# SH2_-_CONNECTORS.net
KiCad netlist of a schematic drawn in Altium Designer
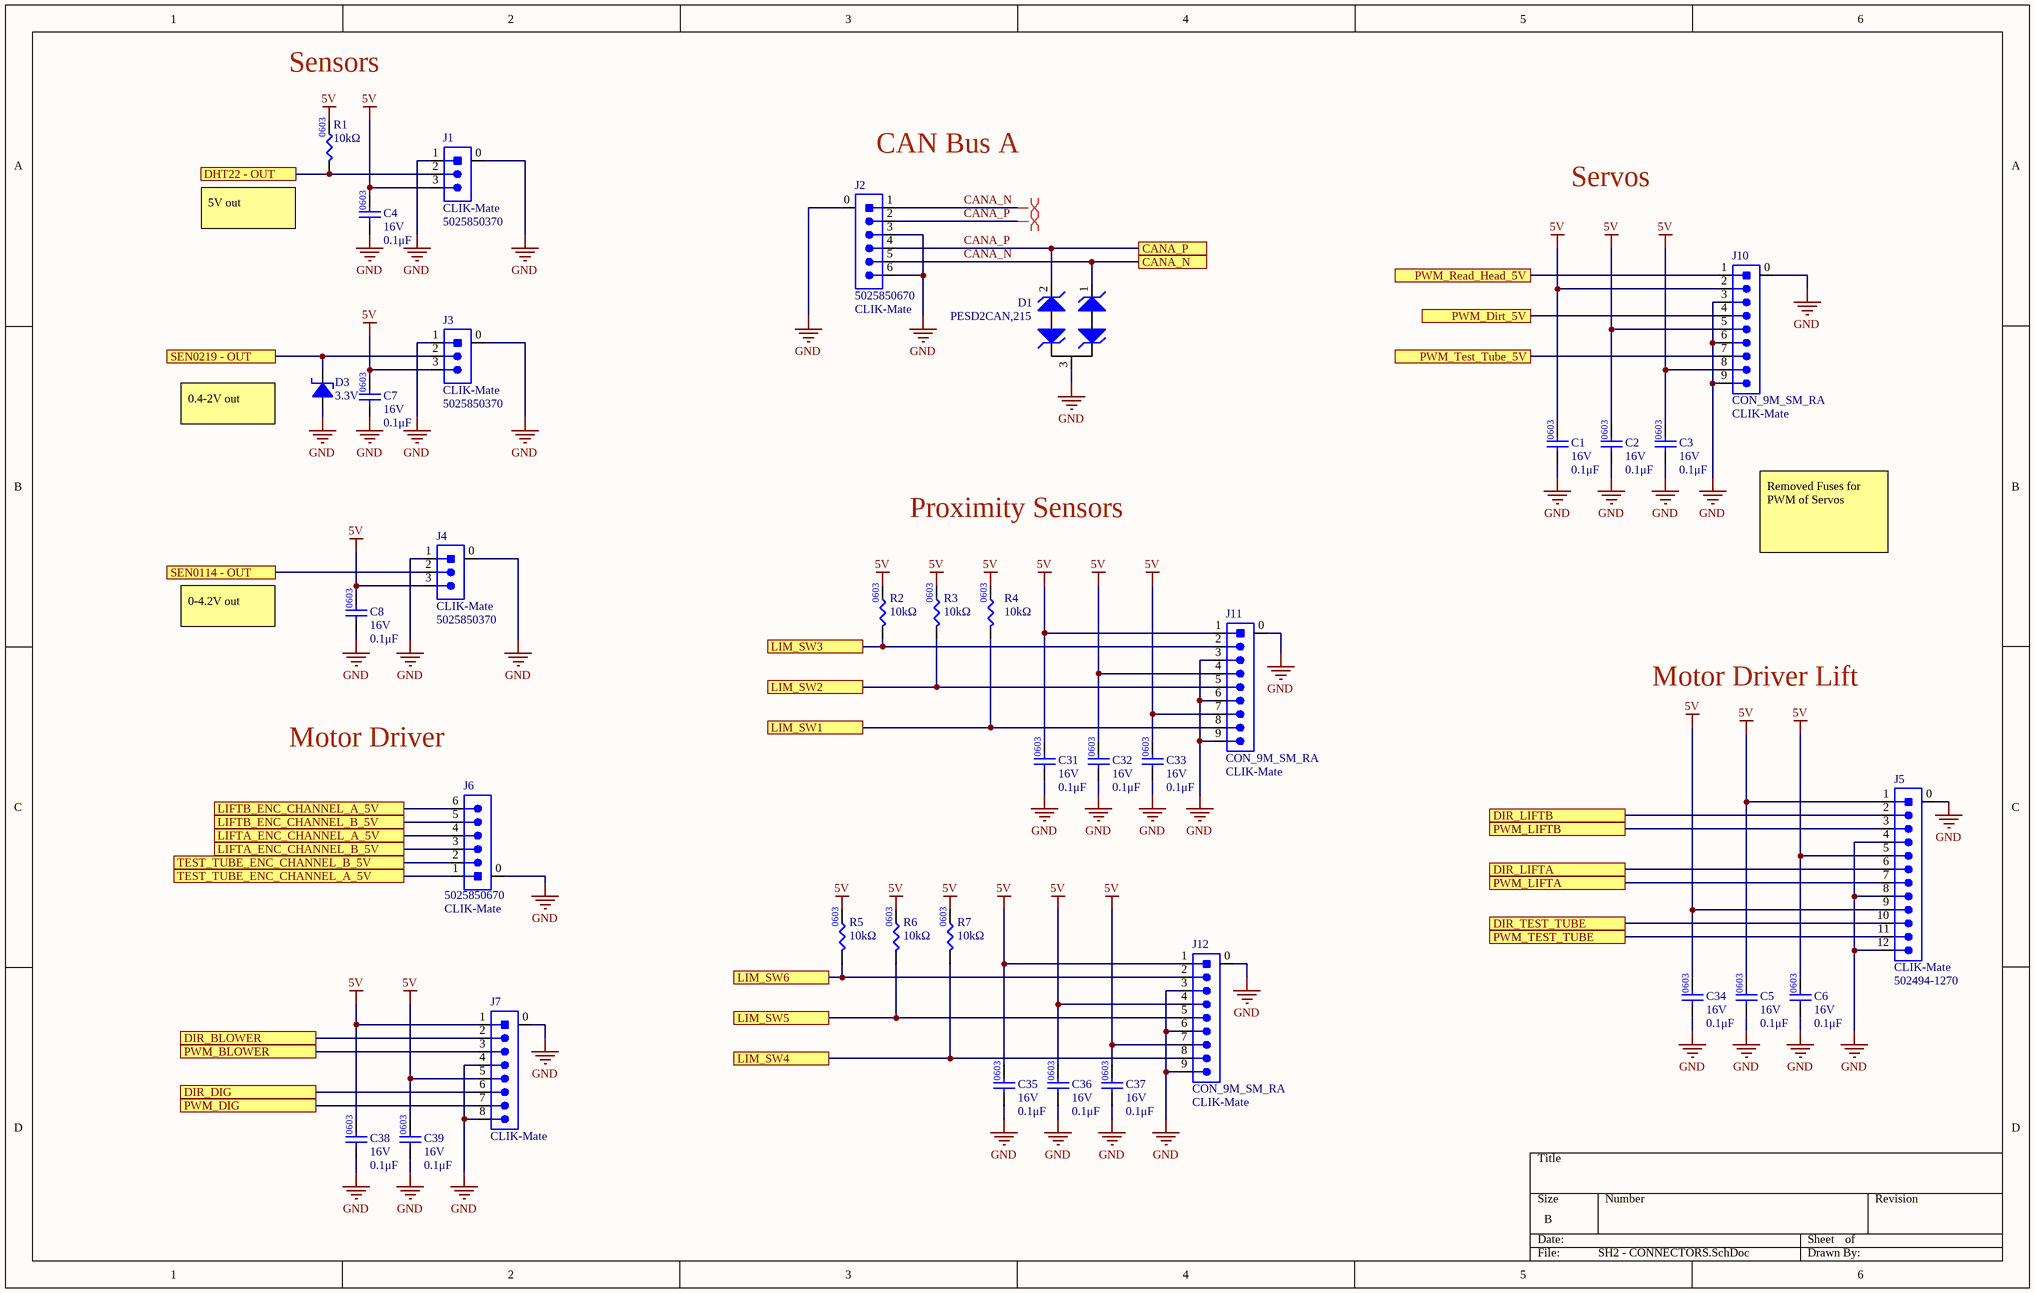
[diagram p0: SH2 - CONNECTORS.SchDoc]

(export (version "E")
  (design (tool "Eeschema 10.0.6"))
  (components
    (comp (ref "C1")
      (value "0.1μF")
      (footprint "CAP0603")
      (description "CAP CER 0.1UF 16V X7R 0603")
      (fields (field (name "VOLTAGE RATING") "16V") (field (name "Comment") "CAP_0.1uF_16V_0603"))
      (libsource (lib "UWRT_Schematic_Library_2020") (part "CAP_0.1uF_16V_0603"))
    )
    (comp (ref "C2")
      (value "0.1μF")
      (footprint "CAP0603")
      (description "CAP CER 0.1UF 16V X7R 0603")
      (fields (field (name "VOLTAGE RATING") "16V") (field (name "Comment") "CAP_0.1uF_16V_0603"))
      (libsource (lib "UWRT_Schematic_Library_2020") (part "CAP_0.1uF_16V_0603"))
    )
    (comp (ref "C3")
      (value "0.1μF")
      (footprint "CAP0603")
      (description "CAP CER 0.1UF 16V X7R 0603")
      (fields (field (name "VOLTAGE RATING") "16V") (field (name "Comment") "CAP_0.1uF_16V_0603"))
      (libsource (lib "UWRT_Schematic_Library_2020") (part "CAP_0.1uF_16V_0603"))
    )
    (comp (ref "C4")
      (value "0.1μF")
      (footprint "CAP0603")
      (description "CAP CER 0.1UF 16V X7R 0603")
      (fields (field (name "VOLTAGE RATING") "16V") (field (name "Comment") "CAP_0.1uF_16V_0603"))
      (libsource (lib "UWRT_Schematic_Library_2020") (part "CAP_0.1uF_16V_0603"))
    )
    (comp (ref "C5")
      (value "0.1μF")
      (footprint "CAP0603")
      (description "CAP CER 0.1UF 16V X7R 0603")
      (fields (field (name "VOLTAGE RATING") "16V") (field (name "Comment") "CAP_0.1uF_16V_0603"))
      (libsource (lib "UWRT_Schematic_Library_2020") (part "CAP_0.1uF_16V_0603"))
    )
    (comp (ref "C6")
      (value "0.1μF")
      (footprint "CAP0603")
      (description "CAP CER 0.1UF 16V X7R 0603")
      (fields (field (name "VOLTAGE RATING") "16V") (field (name "Comment") "CAP_0.1uF_16V_0603"))
      (libsource (lib "UWRT_Schematic_Library_2020") (part "CAP_0.1uF_16V_0603"))
    )
    (comp (ref "C7")
      (value "0.1μF")
      (footprint "CAP0603")
      (description "CAP CER 0.1UF 16V X7R 0603")
      (fields (field (name "VOLTAGE RATING") "16V") (field (name "Comment") "CAP_0.1uF_16V_0603"))
      (libsource (lib "UWRT_Schematic_Library_2020") (part "CAP_0.1uF_16V_0603"))
    )
    (comp (ref "C8")
      (value "0.1μF")
      (footprint "CAP0603")
      (description "CAP CER 0.1UF 16V X7R 0603")
      (fields (field (name "VOLTAGE RATING") "16V") (field (name "Comment") "CAP_0.1uF_16V_0603"))
      (libsource (lib "UWRT_Schematic_Library_2020") (part "CAP_0.1uF_16V_0603"))
    )
    (comp (ref "C31")
      (value "0.1μF")
      (footprint "CAP0603")
      (description "CAP CER 0.1UF 16V X7R 0603")
      (fields (field (name "VOLTAGE RATING") "16V") (field (name "Comment") "CAP_0.1uF_16V_0603"))
      (libsource (lib "UWRT_Schematic_Library_2020") (part "CAP_0.1uF_16V_0603"))
    )
    (comp (ref "C32")
      (value "0.1μF")
      (footprint "CAP0603")
      (description "CAP CER 0.1UF 16V X7R 0603")
      (fields (field (name "VOLTAGE RATING") "16V") (field (name "Comment") "CAP_0.1uF_16V_0603"))
      (libsource (lib "UWRT_Schematic_Library_2020") (part "CAP_0.1uF_16V_0603"))
    )
    (comp (ref "C33")
      (value "0.1μF")
      (footprint "CAP0603")
      (description "CAP CER 0.1UF 16V X7R 0603")
      (fields (field (name "VOLTAGE RATING") "16V") (field (name "Comment") "CAP_0.1uF_16V_0603"))
      (libsource (lib "UWRT_Schematic_Library_2020") (part "CAP_0.1uF_16V_0603"))
    )
    (comp (ref "C34")
      (value "0.1μF")
      (footprint "CAP0603")
      (description "CAP CER 0.1UF 16V X7R 0603")
      (fields (field (name "VOLTAGE RATING") "16V") (field (name "Comment") "CAP_0.1uF_16V_0603"))
      (libsource (lib "UWRT_Schematic_Library_2020") (part "CAP_0.1uF_16V_0603"))
    )
    (comp (ref "C35")
      (value "0.1μF")
      (footprint "CAP0603")
      (description "CAP CER 0.1UF 16V X7R 0603")
      (fields (field (name "VOLTAGE RATING") "16V") (field (name "Comment") "CAP_0.1uF_16V_0603"))
      (libsource (lib "UWRT_Schematic_Library_2020") (part "CAP_0.1uF_16V_0603"))
    )
    (comp (ref "C36")
      (value "0.1μF")
      (footprint "CAP0603")
      (description "CAP CER 0.1UF 16V X7R 0603")
      (fields (field (name "VOLTAGE RATING") "16V") (field (name "Comment") "CAP_0.1uF_16V_0603"))
      (libsource (lib "UWRT_Schematic_Library_2020") (part "CAP_0.1uF_16V_0603"))
    )
    (comp (ref "C37")
      (value "0.1μF")
      (footprint "CAP0603")
      (description "CAP CER 0.1UF 16V X7R 0603")
      (fields (field (name "VOLTAGE RATING") "16V") (field (name "Comment") "CAP_0.1uF_16V_0603"))
      (libsource (lib "UWRT_Schematic_Library_2020") (part "CAP_0.1uF_16V_0603"))
    )
    (comp (ref "C38")
      (value "0.1μF")
      (footprint "CAP0603")
      (description "CAP CER 0.1UF 16V X7R 0603")
      (fields (field (name "VOLTAGE RATING") "16V") (field (name "Comment") "CAP_0.1uF_16V_0603"))
      (libsource (lib "UWRT_Schematic_Library_2020") (part "CAP_0.1uF_16V_0603"))
    )
    (comp (ref "C39")
      (value "0.1μF")
      (footprint "CAP0603")
      (description "CAP CER 0.1UF 16V X7R 0603")
      (fields (field (name "VOLTAGE RATING") "16V") (field (name "Comment") "CAP_0.1uF_16V_0603"))
      (libsource (lib "UWRT_Schematic_Library_2020") (part "CAP_0.1uF_16V_0603"))
    )
    (comp (ref "D1")
      (value "TVS_DIODE_CAN")
      (footprint "TVS_DIODE_CAN")
      (description "TVS DIODE 24V 41V SOT323-3")
      (fields (field (name "MANUFACTURER PART NUMBER 1") "PESD2CAN,215"))
      (libsource (lib "UWRT_Schematic_Library_2020") (part "TVS_DIODE_CAN"))
    )
    (comp (ref "D3")
      (value "DIO_ZENER_3V3")
      (footprint "DIO_ZENER_3V3")
      (description "DIODE ZENER 3.3V 200mW SOD323F")
      (fields (field (name "WORKING VOLTAGE") "3.3V"))
      (libsource (lib "UWRT_Schematic_Library_2020") (part "DIO_ZENER_3V3"))
    )
    (comp (ref "J1")
      (value "CON_3M_SM_RA")
      (footprint "MOLEX-5025850370")
      (description "CONN RCPT 3POS 0.059 TIN SMD R/A")
      (fields (field (name "FAMILY") "CLIK-Mate") (field (name "MANUFACTURER PART NUMBER 1") "5025850370"))
      (libsource (lib "UWRT_Schematic_Library_2020") (part "CON_3M_SM_RA"))
    )
    (comp (ref "J2")
      (value "CON_6M_SM_RA_1.5mm")
      (footprint "MOLEX-5025850670")
      (description "CONN HEADER SMD RIGHT ANGLE 1.5 MM PITCH")
      (fields (field (name "MANUFACTURER PART NUMBER 1") "5025850670") (field (name "FAMILY") "CLIK-Mate"))
      (libsource (lib "") (part "CON_6M_SM_RA_1.5mm_1"))
    )
    (comp (ref "J3")
      (value "CON_3M_SM_RA")
      (footprint "MOLEX-5025850370")
      (description "CONN RCPT 3POS 0.059 TIN SMD R/A")
      (fields (field (name "FAMILY") "CLIK-Mate") (field (name "MANUFACTURER PART NUMBER 1") "5025850370"))
      (libsource (lib "UWRT_Schematic_Library_2020") (part "CON_3M_SM_RA"))
    )
    (comp (ref "J4")
      (value "CON_3M_SM_RA")
      (footprint "MOLEX-5025850370")
      (description "CONN RCPT 3POS 0.059 TIN SMD R/A")
      (fields (field (name "FAMILY") "CLIK-Mate") (field (name "MANUFACTURER PART NUMBER 1") "5025850370"))
      (libsource (lib "UWRT_Schematic_Library_2020") (part "CON_3M_SM_RA"))
    )
    (comp (ref "J5")
      (value "CON_12M_SM_RA_2mm")
      (footprint "MOLEX-5024941270")
      (description "2.00mm Pitch CLIK-Mate Wire-to-Board PCB Receptacle, Single Row, Right-Angle, 12 Circuits")
      (fields
        (field (name "MANUFACTURER") "Molex")
        (field (name "MANUFACTURER PART NUMBER") "502494-1270")
        (field (name "FAMILY") "CLIK-Mate")
        (field (name "SUPPLIER PART NUMBER 1") "502494-1270")
      )
      (libsource (lib "UWRT_Schematic_Library_2020") (part "CON_12M_SM_RA_2mm"))
    )
    (comp (ref "J6")
      (value "CON_6M_SM_RA_1.5mm")
      (footprint "MOLEX-5025850670")
      (description "CONN HEADER SMD RIGHT ANGLE 1.5 MM PITCH")
      (fields (field (name "MANUFACTURER PART NUMBER 1") "5025850670") (field (name "FAMILY") "CLIK-Mate"))
      (libsource (lib "UWRT_Schematic_Library_2020") (part "CON_6M_SM_RA_1.5mm"))
    )
    (comp (ref "J7")
      (value "CON_8M_SM_RA")
      (footprint "5024430870")
      (description "CONN HEADER SMD VERTICAL 2 MM PITCH")
      (fields (field (name "FAMILY") "CLIK-Mate"))
      (libsource (lib "UWRT_Schematic_Library_2020") (part "CON_8M_SM"))
    )
    (comp (ref "J10")
      (value "CON_9M_SM_RA")
      (footprint "Molex-5025850970")
      (description "CONN RCPT 9POS CLIK-MATE 0.059 TIN SMD R/A")
      (fields (field (name "FAMILY") "CLIK-Mate"))
      (libsource (lib "UWRT_Schematic_Library_2020") (part "CON_9M_SM_RA"))
    )
    (comp (ref "J11")
      (value "CON_9M_SM_RA")
      (footprint "Molex-5025850970")
      (description "CONN RCPT 9POS CLIK-MATE 0.059 TIN SMD R/A")
      (fields (field (name "FAMILY") "CLIK-Mate"))
      (libsource (lib "UWRT_Schematic_Library_2020") (part "CON_9M_SM_RA"))
    )
    (comp (ref "J12")
      (value "CON_9M_SM_RA")
      (footprint "Molex-5025850970")
      (description "CONN RCPT 9POS CLIK-MATE 0.059 TIN SMD R/A")
      (fields (field (name "FAMILY") "CLIK-Mate"))
      (libsource (lib "UWRT_Schematic_Library_2020") (part "CON_9M_SM_RA"))
    )
    (comp (ref "R1")
      (value "10kΩ")
      (footprint "RES0603")
      (description "RES 10K OHM 5% 1/10W 0603")
      (fields (field (name "Comment") "RES_10kΩ_0603_5%"))
      (libsource (lib "UWRT_Schematic_Library_2020") (part "RES_10kΩ_0603_5%"))
    )
    (comp (ref "R2")
      (value "10kΩ")
      (footprint "RES0603")
      (description "RES 10K OHM 5% 1/10W 0603")
      (fields (field (name "Comment") "RES_10kΩ_0603_5%"))
      (libsource (lib "UWRT_Schematic_Library_2020") (part "RES_10kΩ_0603_5%"))
    )
    (comp (ref "R3")
      (value "10kΩ")
      (footprint "RES0603")
      (description "RES 10K OHM 5% 1/10W 0603")
      (fields (field (name "Comment") "RES_10kΩ_0603_5%"))
      (libsource (lib "UWRT_Schematic_Library_2020") (part "RES_10kΩ_0603_5%"))
    )
    (comp (ref "R4")
      (value "10kΩ")
      (footprint "RES0603")
      (description "RES 10K OHM 5% 1/10W 0603")
      (fields (field (name "Comment") "RES_10kΩ_0603_5%"))
      (libsource (lib "UWRT_Schematic_Library_2020") (part "RES_10kΩ_0603_5%"))
    )
    (comp (ref "R5")
      (value "10kΩ")
      (footprint "RES0603")
      (description "RES 10K OHM 5% 1/10W 0603")
      (fields (field (name "Comment") "RES_10kΩ_0603_5%"))
      (libsource (lib "UWRT_Schematic_Library_2020") (part "RES_10kΩ_0603_5%"))
    )
    (comp (ref "R6")
      (value "10kΩ")
      (footprint "RES0603")
      (description "RES 10K OHM 5% 1/10W 0603")
      (fields (field (name "Comment") "RES_10kΩ_0603_5%"))
      (libsource (lib "UWRT_Schematic_Library_2020") (part "RES_10kΩ_0603_5%"))
    )
    (comp (ref "R7")
      (value "10kΩ")
      (footprint "RES0603")
      (description "RES 10K OHM 5% 1/10W 0603")
      (fields (field (name "Comment") "RES_10kΩ_0603_5%"))
      (libsource (lib "UWRT_Schematic_Library_2020") (part "RES_10kΩ_0603_5%"))
    )
  )
  (nets
    (net (code "1") (name "/CANA_N") (class "Default")
      (node (ref "D1") (pin "1") (pinfunction "1_1") (pintype "passive"))
      (node (ref "J2") (pin "1") (pinfunction "1_1") (pintype "passive"))
      (node (ref "J2") (pin "5") (pinfunction "5_5") (pintype "passive"))
    )
    (net (code "2") (name "/CANA_P") (class "Default")
      (node (ref "D1") (pin "2") (pinfunction "2_2") (pintype "passive"))
      (node (ref "J2") (pin "2") (pinfunction "2_2") (pintype "passive"))
      (node (ref "J2") (pin "4") (pinfunction "4_4") (pintype "passive"))
    )
    (net (code "3") (name "/DHT22 - OUT") (class "Default")
      (node (ref "J1") (pin "2") (pinfunction "2_2") (pintype "passive"))
      (node (ref "R1") (pin "1") (pinfunction "1_1") (pintype "passive"))
    )
    (net (code "4") (name "/DIR_BLOWER") (class "Default")
      (node (ref "J7") (pin "2") (pinfunction "2_2") (pintype "passive"))
    )
    (net (code "5") (name "/DIR_DIG") (class "Default")
      (node (ref "J7") (pin "6") (pinfunction "6_6") (pintype "passive"))
    )
    (net (code "6") (name "/DIR_LIFTA") (class "Default")
      (node (ref "J5") (pin "6") (pinfunction "6_6") (pintype "passive"))
    )
    (net (code "7") (name "/DIR_LIFTB") (class "Default")
      (node (ref "J5") (pin "2") (pinfunction "2_2") (pintype "passive"))
    )
    (net (code "8") (name "/DIR_TEST_TUBE") (class "Default")
      (node (ref "J5") (pin "10") (pinfunction "10_10") (pintype "passive"))
    )
    (net (code "9") (name "/LIFTA_ENC_CHANNEL_A_5V") (class "Default")
      (node (ref "J6") (pin "4") (pinfunction "4_4") (pintype "passive"))
    )
    (net (code "10") (name "/LIFTA_ENC_CHANNEL_B_5V") (class "Default")
      (node (ref "J6") (pin "3") (pinfunction "3_3") (pintype "passive"))
    )
    (net (code "11") (name "/LIFTB_ENC_CHANNEL_A_5V") (class "Default")
      (node (ref "J6") (pin "6") (pinfunction "6_6") (pintype "passive"))
    )
    (net (code "12") (name "/LIFTB_ENC_CHANNEL_B_5V") (class "Default")
      (node (ref "J6") (pin "5") (pinfunction "5_5") (pintype "passive"))
    )
    (net (code "13") (name "/LIM_SW1") (class "Default")
      (node (ref "J11") (pin "8") (pinfunction "6_8") (pintype "passive"))
      (node (ref "R4") (pin "1") (pinfunction "1_1") (pintype "passive"))
    )
    (net (code "14") (name "/LIM_SW2") (class "Default")
      (node (ref "J11") (pin "5") (pinfunction "5_5") (pintype "passive"))
      (node (ref "R3") (pin "1") (pinfunction "1_1") (pintype "passive"))
    )
    (net (code "15") (name "/LIM_SW3") (class "Default")
      (node (ref "J11") (pin "2") (pinfunction "2_2") (pintype "passive"))
      (node (ref "R2") (pin "1") (pinfunction "1_1") (pintype "passive"))
    )
    (net (code "16") (name "/LIM_SW4") (class "Default")
      (node (ref "J12") (pin "8") (pinfunction "6_8") (pintype "passive"))
      (node (ref "R7") (pin "1") (pinfunction "1_1") (pintype "passive"))
    )
    (net (code "17") (name "/LIM_SW5") (class "Default")
      (node (ref "J12") (pin "5") (pinfunction "5_5") (pintype "passive"))
      (node (ref "R6") (pin "1") (pinfunction "1_1") (pintype "passive"))
    )
    (net (code "18") (name "/LIM_SW6") (class "Default")
      (node (ref "J12") (pin "2") (pinfunction "2_2") (pintype "passive"))
      (node (ref "R5") (pin "1") (pinfunction "1_1") (pintype "passive"))
    )
    (net (code "19") (name "/PWM_BLOWER") (class "Default")
      (node (ref "J7") (pin "3") (pinfunction "3_3") (pintype "passive"))
    )
    (net (code "20") (name "/PWM_DIG") (class "Default")
      (node (ref "J7") (pin "7") (pinfunction "6_7") (pintype "passive"))
    )
    (net (code "21") (name "/PWM_Dirt_5V") (class "Default")
      (node (ref "J10") (pin "4") (pinfunction "4_4") (pintype "passive"))
    )
    (net (code "22") (name "/PWM_LIFTA") (class "Default")
      (node (ref "J5") (pin "7") (pinfunction "6_7") (pintype "passive"))
    )
    (net (code "23") (name "/PWM_LIFTB") (class "Default")
      (node (ref "J5") (pin "3") (pinfunction "3_3") (pintype "passive"))
    )
    (net (code "24") (name "/PWM_Read_Head_5V") (class "Default")
      (node (ref "J10") (pin "1") (pinfunction "1_1") (pintype "passive"))
    )
    (net (code "25") (name "/PWM_TEST_TUBE") (class "Default")
      (node (ref "J5") (pin "11") (pinfunction "11_11") (pintype "passive"))
    )
    (net (code "26") (name "/PWM_Test_Tube_5V") (class "Default")
      (node (ref "J10") (pin "7") (pinfunction "6_7") (pintype "passive"))
    )
    (net (code "27") (name "/SEN0114 - OUT") (class "Default")
      (node (ref "J4") (pin "2") (pinfunction "2_2") (pintype "passive"))
    )
    (net (code "28") (name "/SEN0219 - OUT") (class "Default")
      (node (ref "D3") (pin "2") (pinfunction "Cathode_2") (pintype "passive"))
      (node (ref "J3") (pin "2") (pinfunction "2_2") (pintype "passive"))
    )
    (net (code "29") (name "/TEST_TUBE_ENC_CHANNEL_A_5V") (class "Default")
      (node (ref "J6") (pin "1") (pinfunction "1_1") (pintype "passive"))
    )
    (net (code "30") (name "/TEST_TUBE_ENC_CHANNEL_B_5V") (class "Default")
      (node (ref "J6") (pin "2") (pinfunction "2_2") (pintype "passive"))
    )
    (net (code "31") (name "5V") (class "Default")
      (node (ref "C1") (pin "2") (pinfunction "2_2") (pintype "passive"))
      (node (ref "C2") (pin "2") (pinfunction "2_2") (pintype "passive"))
      (node (ref "C3") (pin "2") (pinfunction "2_2") (pintype "passive"))
      (node (ref "C31") (pin "2") (pinfunction "2_2") (pintype "passive"))
      (node (ref "C32") (pin "2") (pinfunction "2_2") (pintype "passive"))
      (node (ref "C33") (pin "2") (pinfunction "2_2") (pintype "passive"))
      (node (ref "C34") (pin "2") (pinfunction "2_2") (pintype "passive"))
      (node (ref "C35") (pin "2") (pinfunction "2_2") (pintype "passive"))
      (node (ref "C36") (pin "2") (pinfunction "2_2") (pintype "passive"))
      (node (ref "C37") (pin "2") (pinfunction "2_2") (pintype "passive"))
      (node (ref "C38") (pin "2") (pinfunction "2_2") (pintype "passive"))
      (node (ref "C39") (pin "2") (pinfunction "2_2") (pintype "passive"))
      (node (ref "C4") (pin "2") (pinfunction "2_2") (pintype "passive"))
      (node (ref "C5") (pin "2") (pinfunction "2_2") (pintype "passive"))
      (node (ref "C6") (pin "2") (pinfunction "2_2") (pintype "passive"))
      (node (ref "C7") (pin "2") (pinfunction "2_2") (pintype "passive"))
      (node (ref "C8") (pin "2") (pinfunction "2_2") (pintype "passive"))
      (node (ref "J1") (pin "3") (pinfunction "3_3") (pintype "passive"))
      (node (ref "J10") (pin "2") (pinfunction "2_2") (pintype "passive"))
      (node (ref "J10") (pin "5") (pinfunction "5_5") (pintype "passive"))
      (node (ref "J10") (pin "8") (pinfunction "6_8") (pintype "passive"))
      (node (ref "J11") (pin "1") (pinfunction "1_1") (pintype "passive"))
      (node (ref "J11") (pin "4") (pinfunction "4_4") (pintype "passive"))
      (node (ref "J11") (pin "7") (pinfunction "6_7") (pintype "passive"))
      (node (ref "J12") (pin "1") (pinfunction "1_1") (pintype "passive"))
      (node (ref "J12") (pin "4") (pinfunction "4_4") (pintype "passive"))
      (node (ref "J12") (pin "7") (pinfunction "6_7") (pintype "passive"))
      (node (ref "J3") (pin "3") (pinfunction "3_3") (pintype "passive"))
      (node (ref "J4") (pin "3") (pinfunction "3_3") (pintype "passive"))
      (node (ref "J5") (pin "1") (pinfunction "1_1") (pintype "passive"))
      (node (ref "J5") (pin "5") (pinfunction "5_5") (pintype "passive"))
      (node (ref "J5") (pin "9") (pinfunction "9_9") (pintype "passive"))
      (node (ref "J7") (pin "1") (pinfunction "1_1") (pintype "passive"))
      (node (ref "J7") (pin "5") (pinfunction "5_5") (pintype "passive"))
      (node (ref "R1") (pin "2") (pinfunction "2_2") (pintype "passive"))
      (node (ref "R2") (pin "2") (pinfunction "2_2") (pintype "passive"))
      (node (ref "R3") (pin "2") (pinfunction "2_2") (pintype "passive"))
      (node (ref "R4") (pin "2") (pinfunction "2_2") (pintype "passive"))
      (node (ref "R5") (pin "2") (pinfunction "2_2") (pintype "passive"))
      (node (ref "R6") (pin "2") (pinfunction "2_2") (pintype "passive"))
      (node (ref "R7") (pin "2") (pinfunction "2_2") (pintype "passive"))
    )
    (net (code "32") (name "GND") (class "Default")
      (node (ref "C1") (pin "1") (pinfunction "1_1") (pintype "passive"))
      (node (ref "C2") (pin "1") (pinfunction "1_1") (pintype "passive"))
      (node (ref "C3") (pin "1") (pinfunction "1_1") (pintype "passive"))
      (node (ref "C31") (pin "1") (pinfunction "1_1") (pintype "passive"))
      (node (ref "C32") (pin "1") (pinfunction "1_1") (pintype "passive"))
      (node (ref "C33") (pin "1") (pinfunction "1_1") (pintype "passive"))
      (node (ref "C34") (pin "1") (pinfunction "1_1") (pintype "passive"))
      (node (ref "C35") (pin "1") (pinfunction "1_1") (pintype "passive"))
      (node (ref "C36") (pin "1") (pinfunction "1_1") (pintype "passive"))
      (node (ref "C37") (pin "1") (pinfunction "1_1") (pintype "passive"))
      (node (ref "C38") (pin "1") (pinfunction "1_1") (pintype "passive"))
      (node (ref "C39") (pin "1") (pinfunction "1_1") (pintype "passive"))
      (node (ref "C4") (pin "1") (pinfunction "1_1") (pintype "passive"))
      (node (ref "C5") (pin "1") (pinfunction "1_1") (pintype "passive"))
      (node (ref "C6") (pin "1") (pinfunction "1_1") (pintype "passive"))
      (node (ref "C7") (pin "1") (pinfunction "1_1") (pintype "passive"))
      (node (ref "C8") (pin "1") (pinfunction "1_1") (pintype "passive"))
      (node (ref "D1") (pin "3") (pinfunction "3_3") (pintype "passive"))
      (node (ref "D3") (pin "1") (pinfunction "Anode_1") (pintype "passive"))
      (node (ref "J1") (pin "0") (pinfunction "0_0") (pintype "passive"))
      (node (ref "J1") (pin "1") (pinfunction "1_1") (pintype "passive"))
      (node (ref "J10") (pin "0") (pinfunction "0_0") (pintype "passive"))
      (node (ref "J10") (pin "3") (pinfunction "3_3") (pintype "passive"))
      (node (ref "J10") (pin "6") (pinfunction "6_6") (pintype "passive"))
      (node (ref "J10") (pin "9") (pinfunction "9_9") (pintype "passive"))
      (node (ref "J11") (pin "0") (pinfunction "0_0") (pintype "passive"))
      (node (ref "J11") (pin "3") (pinfunction "3_3") (pintype "passive"))
      (node (ref "J11") (pin "6") (pinfunction "6_6") (pintype "passive"))
      (node (ref "J11") (pin "9") (pinfunction "9_9") (pintype "passive"))
      (node (ref "J12") (pin "0") (pinfunction "0_0") (pintype "passive"))
      (node (ref "J12") (pin "3") (pinfunction "3_3") (pintype "passive"))
      (node (ref "J12") (pin "6") (pinfunction "6_6") (pintype "passive"))
      (node (ref "J12") (pin "9") (pinfunction "9_9") (pintype "passive"))
      (node (ref "J2") (pin "0") (pinfunction "0_0") (pintype "passive"))
      (node (ref "J2") (pin "3") (pinfunction "3_3") (pintype "passive"))
      (node (ref "J2") (pin "6") (pinfunction "6_6") (pintype "passive"))
      (node (ref "J3") (pin "0") (pinfunction "0_0") (pintype "passive"))
      (node (ref "J3") (pin "1") (pinfunction "1_1") (pintype "passive"))
      (node (ref "J4") (pin "0") (pinfunction "0_0") (pintype "passive"))
      (node (ref "J4") (pin "1") (pinfunction "1_1") (pintype "passive"))
      (node (ref "J5") (pin "0") (pinfunction "0_0") (pintype "passive"))
      (node (ref "J5") (pin "12") (pinfunction "12_12") (pintype "passive"))
      (node (ref "J5") (pin "4") (pinfunction "4_4") (pintype "passive"))
      (node (ref "J5") (pin "8") (pinfunction "6_8") (pintype "passive"))
      (node (ref "J6") (pin "0") (pinfunction "0_0") (pintype "passive"))
      (node (ref "J7") (pin "0") (pinfunction "0_0") (pintype "passive"))
      (node (ref "J7") (pin "4") (pinfunction "4_4") (pintype "passive"))
      (node (ref "J7") (pin "8") (pinfunction "6_8") (pintype "passive"))
    )
  )
)
